# brick_i2c_9axis_MPU9250.net
KiCad netlist of a schematic drawn in EAGLE
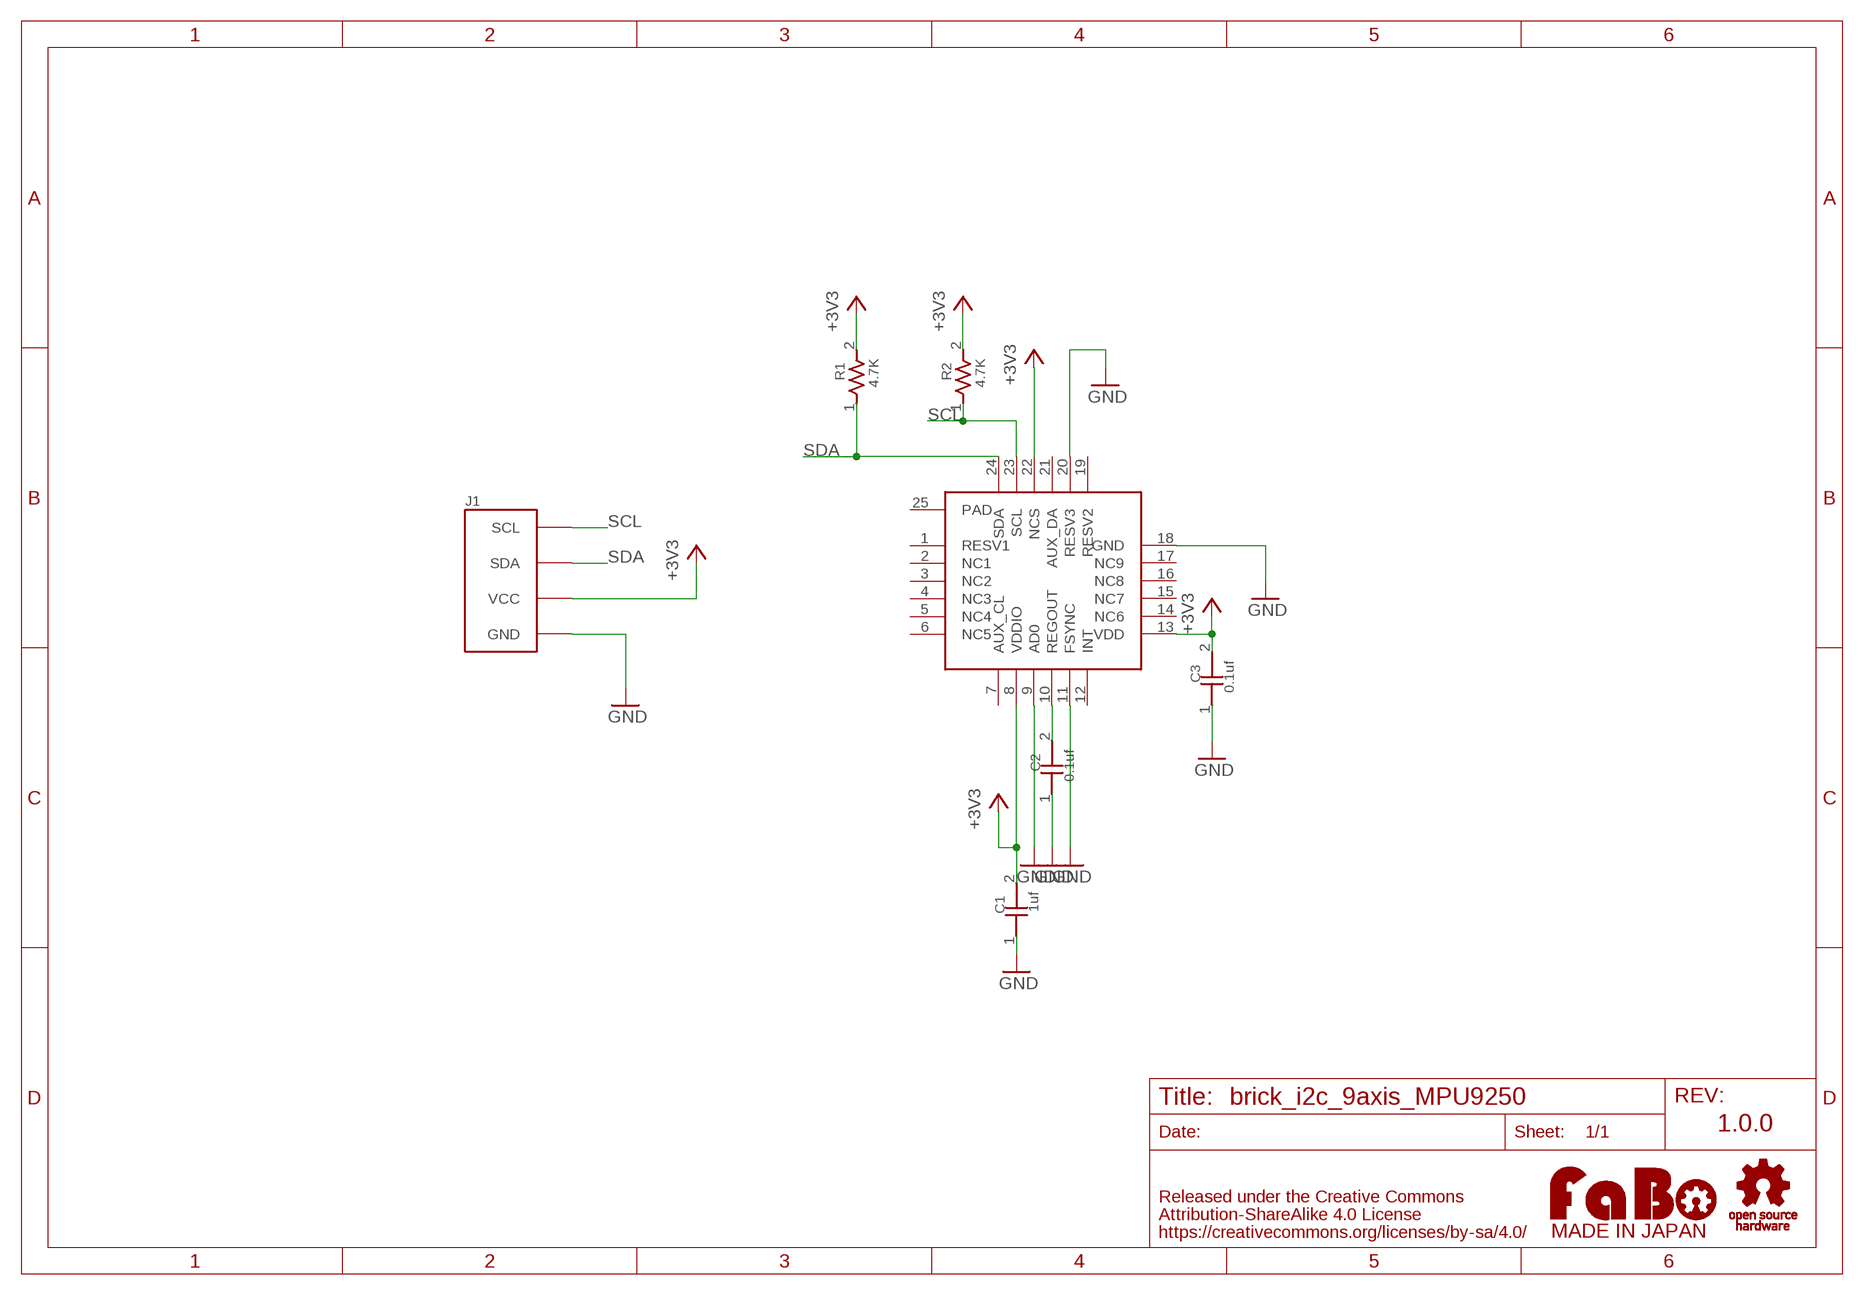
[diagram p0: schematic, sheet 1]

(export (version "E")
  (design (tool "Eeschema 10.0.6"))
  (components
    (comp (ref "C1")
      (value "1uf")
      (footprint "eagle-import:0603")
      (libsource (lib "eagle-import") (part "CAPACITOR0603"))
    )
    (comp (ref "C2")
      (value "0.1uf")
      (footprint "eagle-import:0603")
      (libsource (lib "eagle-import") (part "CAPACITOR0603"))
    )
    (comp (ref "C3")
      (value "0.1uf")
      (footprint "eagle-import:0603")
      (libsource (lib "eagle-import") (part "CAPACITOR0603"))
    )
    (comp (ref "J1")
      (value "BRICK_I2C")
      (footprint "eagle-import:BRICK_I2C")
      (libsource (lib "eagle-import") (part "BRICK_I2C"))
    )
    (comp (ref "R1")
      (value "4.7K")
      (footprint "eagle-import:0603")
      (libsource (lib "eagle-import") (part "RESISTOR0603"))
    )
    (comp (ref "R2")
      (value "4.7K")
      (footprint "eagle-import:0603")
      (libsource (lib "eagle-import") (part "RESISTOR0603"))
    )
    (comp (ref "U$1")
      (value "INVENSENSE-MPU9250")
      (footprint "eagle-import:LGA-24")
      (libsource (lib "eagle-import") (part "INVENSENSE-MPU9250"))
    )
    (comp (ref "U$3")
      (value "LOGO_FABO-M")
      (footprint "eagle-import:LOGO_FABO_M")
      (libsource (lib "eagle-import") (part "LOGO_FABO-M"))
    )
    (comp (ref "U$5")
      (value "LOGO_OSHW_T-M")
      (footprint "eagle-import:LOGO_OSHW_T_M")
      (libsource (lib "eagle-import") (part "LOGO_OSHW_T-M"))
    )
  )
  (nets
    (net (code "1") (name "+3V3") (class "Default")
      (node (ref "C1") (pin "2") (pinfunction "2_2") (pintype "passive"))
      (node (ref "C3") (pin "2") (pinfunction "2_2") (pintype "passive"))
      (node (ref "J1") (pin "VCC") (pinfunction "VCC_VCC") (pintype "bidirectional"))
      (node (ref "R1") (pin "2") (pinfunction "2_2") (pintype "passive"))
      (node (ref "R2") (pin "2") (pinfunction "2_2") (pintype "passive"))
      (node (ref "U$1") (pin "13") (pinfunction "VDD_13") (pintype "bidirectional"))
      (node (ref "U$1") (pin "22") (pinfunction "NCS_22") (pintype "bidirectional"))
      (node (ref "U$1") (pin "8") (pinfunction "VDDIO_8") (pintype "bidirectional"))
    )
    (net (code "2") (name "/SCL") (class "Default")
      (node (ref "J1") (pin "SCL") (pinfunction "SCL_SCL") (pintype "bidirectional"))
      (node (ref "R2") (pin "1") (pinfunction "1_1") (pintype "passive"))
      (node (ref "U$1") (pin "23") (pinfunction "SCL_23") (pintype "bidirectional"))
    )
    (net (code "3") (name "/SDA") (class "Default")
      (node (ref "J1") (pin "SDA") (pinfunction "SDA_SDA") (pintype "bidirectional"))
      (node (ref "R1") (pin "1") (pinfunction "1_1") (pintype "passive"))
      (node (ref "U$1") (pin "24") (pinfunction "SDA_24") (pintype "bidirectional"))
    )
    (net (code "4") (name "GND") (class "Default")
      (node (ref "C1") (pin "1") (pinfunction "1_1") (pintype "passive"))
      (node (ref "C2") (pin "1") (pinfunction "1_1") (pintype "passive"))
      (node (ref "C3") (pin "1") (pinfunction "1_1") (pintype "passive"))
      (node (ref "J1") (pin "GND") (pinfunction "GND_GND") (pintype "bidirectional"))
      (node (ref "U$1") (pin "11") (pinfunction "FSYNC_11") (pintype "bidirectional"))
      (node (ref "U$1") (pin "18") (pinfunction "GND_18") (pintype "bidirectional"))
      (node (ref "U$1") (pin "20") (pinfunction "RESV3_20") (pintype "bidirectional"))
      (node (ref "U$1") (pin "9") (pinfunction "AD0_9") (pintype "bidirectional"))
    )
    (net (code "5") (name "Net-(U$1-REGOUT)") (class "Default")
      (node (ref "C2") (pin "2") (pinfunction "2_2") (pintype "passive"))
      (node (ref "U$1") (pin "10") (pinfunction "REGOUT_10") (pintype "bidirectional"))
    )
    (net (code "6") (name "unconnected-(U$1-AUX_CL-Pad7)") (class "Default")
      (node (ref "U$1") (pin "7") (pinfunction "AUX_CL_7") (pintype "bidirectional"))
    )
    (net (code "7") (name "unconnected-(U$1-AUX_DA-Pad21)") (class "Default")
      (node (ref "U$1") (pin "21") (pinfunction "AUX_DA_21") (pintype "bidirectional"))
    )
    (net (code "8") (name "unconnected-(U$1-INT-Pad12)") (class "Default")
      (node (ref "U$1") (pin "12") (pinfunction "INT_12") (pintype "bidirectional"))
    )
    (net (code "9") (name "unconnected-(U$1-NC1-Pad2)") (class "Default")
      (node (ref "U$1") (pin "2") (pinfunction "NC1_2") (pintype "bidirectional"))
    )
    (net (code "10") (name "unconnected-(U$1-NC2-Pad3)") (class "Default")
      (node (ref "U$1") (pin "3") (pinfunction "NC2_3") (pintype "bidirectional"))
    )
    (net (code "11") (name "unconnected-(U$1-NC3-Pad4)") (class "Default")
      (node (ref "U$1") (pin "4") (pinfunction "NC3_4") (pintype "bidirectional"))
    )
    (net (code "12") (name "unconnected-(U$1-NC4-Pad5)") (class "Default")
      (node (ref "U$1") (pin "5") (pinfunction "NC4_5") (pintype "bidirectional"))
    )
    (net (code "13") (name "unconnected-(U$1-NC5-Pad6)") (class "Default")
      (node (ref "U$1") (pin "6") (pinfunction "NC5_6") (pintype "bidirectional"))
    )
    (net (code "14") (name "unconnected-(U$1-NC6-Pad14)") (class "Default")
      (node (ref "U$1") (pin "14") (pinfunction "NC6_14") (pintype "bidirectional"))
    )
    (net (code "15") (name "unconnected-(U$1-NC7-Pad15)") (class "Default")
      (node (ref "U$1") (pin "15") (pinfunction "NC7_15") (pintype "bidirectional"))
    )
    (net (code "16") (name "unconnected-(U$1-NC8-Pad16)") (class "Default")
      (node (ref "U$1") (pin "16") (pinfunction "NC8_16") (pintype "bidirectional"))
    )
    (net (code "17") (name "unconnected-(U$1-NC9-Pad17)") (class "Default")
      (node (ref "U$1") (pin "17") (pinfunction "NC9_17") (pintype "bidirectional"))
    )
    (net (code "18") (name "unconnected-(U$1-PAD-Pad25)") (class "Default")
      (node (ref "U$1") (pin "25") (pinfunction "PAD_25") (pintype "bidirectional"))
    )
    (net (code "19") (name "unconnected-(U$1-RESV1-Pad1)") (class "Default")
      (node (ref "U$1") (pin "1") (pinfunction "RESV1_1") (pintype "bidirectional"))
    )
    (net (code "20") (name "unconnected-(U$1-RESV2-Pad19)") (class "Default")
      (node (ref "U$1") (pin "19") (pinfunction "RESV2_19") (pintype "bidirectional"))
    )
  )
)
